# USB.net
KiCad netlist of a schematic drawn in Altium Designer
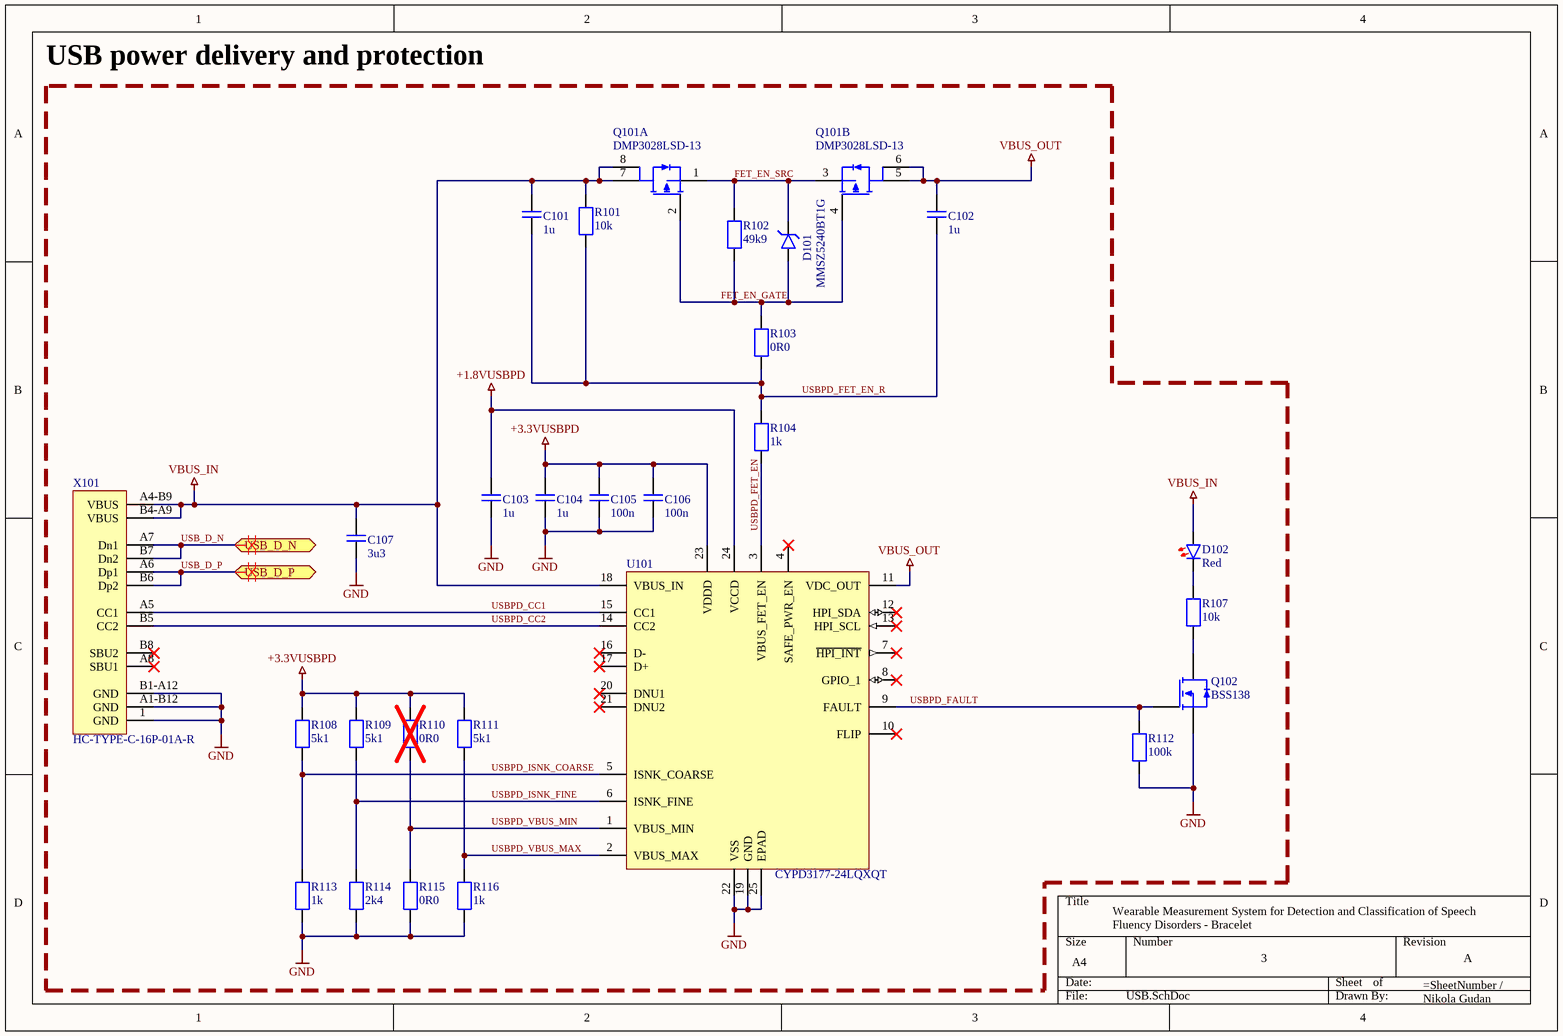
[diagram p0: USB.SchDoc]

(export (version "E")
  (design (tool "Eeschema 10.0.6"))
  (components
    (comp (ref "C101")
      (value "1u")
      (footprint "CAPC0603")
      (description "Ceramic capacitor, 1uF,  50V, X5R")
      (fields (field (name "MFR") "Murata Electronics") (field (name "CHECKED") "Yes"))
      (libsource (lib "NG_Passive") (part "CAPC0603-1u-10"))
    )
    (comp (ref "C102")
      (value "1u")
      (footprint "CAPC0603")
      (description "Ceramic capacitor, 1uF,  50V, X5R")
      (fields (field (name "MFR") "Murata Electronics") (field (name "CHECKED") "Yes"))
      (libsource (lib "NG_Passive") (part "CAPC0603-1u-10"))
    )
    (comp (ref "C103")
      (value "1u")
      (footprint "CAPC0603")
      (description "Ceramic capacitor, 1uF,  50V, X5R")
      (fields (field (name "MFR") "Murata Electronics") (field (name "CHECKED") "Yes"))
      (libsource (lib "NG_Passive") (part "CAPC0603-1u-10"))
    )
    (comp (ref "C104")
      (value "1u")
      (footprint "CAPC0603")
      (description "Ceramic capacitor, 1uF,  50V, X5R")
      (fields (field (name "MFR") "Murata Electronics") (field (name "CHECKED") "Yes"))
      (libsource (lib "NG_Passive") (part "CAPC0603-1u-10"))
    )
    (comp (ref "C105")
      (value "100n")
      (footprint "CAPC0603")
      (description "Ceramic capacitor, 100nF,  50V, X7R")
      (fields (field (name "MFR") "KEMET") (field (name "CHECKED") "Yes"))
      (libsource (lib "NG_Passive") (part "CAPC0603-100n-10"))
    )
    (comp (ref "C106")
      (value "100n")
      (footprint "CAPC0603")
      (description "Ceramic capacitor, 100nF,  50V, X7R")
      (fields (field (name "MFR") "KEMET") (field (name "CHECKED") "Yes"))
      (libsource (lib "NG_Passive") (part "CAPC0603-100n-10"))
    )
    (comp (ref "C107")
      (value "3u3")
      (footprint "CAPC0603")
      (description "Ceramic capacitor, 3.3uF,  25V, X5R")
      (fields (field (name "MFR") "TDK") (field (name "CHECKED") "Yes"))
      (libsource (lib "NG_Passive") (part "CAPC0603-3u3-10"))
    )
    (comp (ref "D101")
      (value "MMSZ5240BT1G")
      (footprint "SODFL368160X117")
      (description "Zener Dioode, 10V, 500mW")
      (fields (field (name "MFR") "onsemi") (field (name "CHECKED") "Yes"))
      (libsource (lib "NG_Active") (part "MMSZ5240BT1G"))
    )
    (comp (ref "D102")
      (value "Red")
      (footprint "LED0603")
      (description "LED Red, 2.3V, 20mA")
      (fields (field (name "MFR") "Würth Elektronik") (field (name "CHECKED") "Yes"))
      (libsource (lib "NG_Active") (part "150060RS75000"))
    )
    (comp (ref "Q101")
      (value "DMP3028LSD-13")
      (footprint "SOIC127P620X175-8")
      (description "MOSFET, 2P-CH, 30V, 6A")
      (fields (field (name "MFR") "Diodes Incorporated") (field (name "CHECKED") "Yes"))
      (libsource (lib "NG_Active") (part "DMP3028LSD-13"))
    )
    (comp (ref "Q102")
      (value "BSS138")
      (footprint "SOT190P240X290-3")
      (description "MOSFET, N-CH, 50V, 220mA")
      (fields (field (name "MFR") "onsemi") (field (name "CHECKED") "Yes"))
      (libsource (lib "NG_Active") (part "BSS138"))
    )
    (comp (ref "R101")
      (value "10k")
      (footprint "RESC0603")
      (description "Thick film resistor, 10kOhm, 100mW")
      (fields (field (name "MFR") "YAGEO") (field (name "CHECKED") "Yes"))
      (libsource (lib "NG_Passive") (part "RES0603-10k-1"))
    )
    (comp (ref "R102")
      (value "49k9")
      (footprint "RESC0603")
      (description "Thick film resistor, 49.9kOhms, 100mW")
      (fields (field (name "MFR") "YAGEO") (field (name "CHECKED") "Yes"))
      (libsource (lib "NG_Passive") (part "RES0603-49k9-1"))
    )
    (comp (ref "R103")
      (value "0R0")
      (footprint "RESC0603")
      (description "Thick film resistor, 0Ohms, 100mW")
      (fields (field (name "MFR") "YAGEO") (field (name "CHECKED") "Yes"))
      (libsource (lib "NG_Passive") (part "RES0603-0R0-1"))
    )
    (comp (ref "R104")
      (value "1k")
      (footprint "RESC0603")
      (description "Thick film resistor, 1k, 100mW")
      (fields (field (name "MFR") "YAGEO") (field (name "CHECKED") "Yes"))
      (libsource (lib "NG_Passive") (part "RES0603-1k-1"))
    )
    (comp (ref "R107")
      (value "10k")
      (footprint "RESC0603")
      (description "Thick film resistor, 10kOhm, 100mW")
      (fields (field (name "MFR") "YAGEO") (field (name "CHECKED") "Yes"))
      (libsource (lib "NG_Passive") (part "RES0603-10k-1"))
    )
    (comp (ref "R108")
      (value "5k1")
      (footprint "RESC0603")
      (description "Thick film resistor, 5.1kOhms, 100mW")
      (fields (field (name "MFR") "YAGEO") (field (name "CHECKED") "Yes"))
      (libsource (lib "NG_Passive") (part "RES0603-5k1-1"))
    )
    (comp (ref "R109")
      (value "5k1")
      (footprint "RESC0603")
      (description "Thick film resistor, 5.1kOhms, 100mW")
      (fields (field (name "MFR") "YAGEO") (field (name "CHECKED") "Yes"))
      (libsource (lib "NG_Passive") (part "RES0603-5k1-1"))
    )
    (comp (ref "R110")
      (value "0R0")
      (footprint "RESC0603")
      (description "Thick film resistor, 0Ohms, 100mW")
      (fields (field (name "MFR") "YAGEO") (field (name "CHECKED") "Yes"))
      (libsource (lib "NG_Passive") (part "RES0603-0R0-1"))
    )
    (comp (ref "R111")
      (value "5k1")
      (footprint "RESC0603")
      (description "Thick film resistor, 5.1kOhms, 100mW")
      (fields (field (name "MFR") "YAGEO") (field (name "CHECKED") "Yes"))
      (libsource (lib "NG_Passive") (part "RES0603-5k1-1"))
    )
    (comp (ref "R112")
      (value "100k")
      (footprint "RESC0603")
      (description "Thick film resistor, 100kOhms, 100mW")
      (fields (field (name "MFR") "YAGEO") (field (name "CHECKED") "Yes"))
      (libsource (lib "NG_Passive") (part "RES0603-100k-1"))
    )
    (comp (ref "R113")
      (value "1k")
      (footprint "RESC0603")
      (description "Thick film resistor, 1k, 100mW")
      (fields (field (name "MFR") "YAGEO") (field (name "CHECKED") "Yes"))
      (libsource (lib "NG_Passive") (part "RES0603-1k-1"))
    )
    (comp (ref "R114")
      (value "2k4")
      (footprint "RESC0603")
      (description "Thick film resistor, 2.4kOhms, 100mW")
      (fields (field (name "MFR") "YAGEO") (field (name "CHECKED") "Yes"))
      (libsource (lib "NG_Passive") (part "RES0603-2k4-1"))
    )
    (comp (ref "R115")
      (value "0R0")
      (footprint "RESC0603")
      (description "Thick film resistor, 0Ohms, 100mW")
      (fields (field (name "MFR") "YAGEO") (field (name "CHECKED") "Yes"))
      (libsource (lib "NG_Passive") (part "RES0603-0R0-1"))
    )
    (comp (ref "R116")
      (value "1k")
      (footprint "RESC0603")
      (description "Thick film resistor, 1k, 100mW")
      (fields (field (name "MFR") "YAGEO") (field (name "CHECKED") "Yes"))
      (libsource (lib "NG_Passive") (part "RES0603-1k-1"))
    )
    (comp (ref "U101")
      (value "CYPD3177-24LQXQT")
      (footprint "QFN50P410X410X100-24EP")
      (description "Generic Description")
      (fields (field (name "MFR") "Infineon Technologies") (field (name "CHECKED") "Yes"))
      (libsource (lib "NG_Analog") (part "CYPD3177-24LQXQT"))
    )
    (comp (ref "X101")
      (value "HC-TYPE-C-16P-01A-R")
      (footprint "GCT_USB4105-GF-A")
      (description "USB TYPE-C 3.1, 3A")
      (fields (field (name "MFR") "GCT") (field (name "CHECKED") "Yes"))
      (libsource (lib "NG_Mechanical") (part "CONN USB 2.0 TYPE C"))
    )
  )
  (nets
    (net (code "1") (name "+1.8VUSBPD") (class "Default")
      (node (ref "C103") (pin "2") (pinfunction "2_2") (pintype "passive"))
      (node (ref "U101") (pin "24") (pinfunction "VCCD_24") (pintype "power_in"))
    )
    (net (code "2") (name "+3.3VUSBPD") (class "Default")
      (node (ref "C104") (pin "2") (pinfunction "2_2") (pintype "passive"))
      (node (ref "C105") (pin "2") (pinfunction "2_2") (pintype "passive"))
      (node (ref "C106") (pin "2") (pinfunction "2_2") (pintype "passive"))
      (node (ref "R108") (pin "2") (pinfunction "2_2") (pintype "passive"))
      (node (ref "R109") (pin "2") (pinfunction "2_2") (pintype "passive"))
      (node (ref "R110") (pin "2") (pinfunction "2_2") (pintype "passive"))
      (node (ref "R111") (pin "2") (pinfunction "2_2") (pintype "passive"))
      (node (ref "U101") (pin "23") (pinfunction "VDDD_23") (pintype "power_in"))
    )
    (net (code "3") (name "/FET_EN_GATE") (class "Default")
      (node (ref "D101") (pin "2") (pinfunction "2_2") (pintype "passive"))
      (node (ref "Q101") (pin "2") (pinfunction "G1_2") (pintype "power_in"))
      (node (ref "Q101") (pin "4") (pinfunction "G2_4") (pintype "power_in"))
      (node (ref "R102") (pin "1") (pinfunction "1_1") (pintype "passive"))
      (node (ref "R103") (pin "2") (pinfunction "2_2") (pintype "passive"))
    )
    (net (code "4") (name "/FET_EN_SRC") (class "Default")
      (node (ref "D101") (pin "1") (pinfunction "1_1") (pintype "passive"))
      (node (ref "Q101") (pin "1") (pinfunction "S1_1") (pintype "power_in"))
      (node (ref "Q101") (pin "3") (pinfunction "S2_3") (pintype "power_in"))
      (node (ref "R102") (pin "2") (pinfunction "2_2") (pintype "passive"))
    )
    (net (code "5") (name "/USBPD_CC1") (class "Default")
      (node (ref "U101") (pin "15") (pinfunction "CC1_15") (pintype "passive"))
      (node (ref "X101") (pin "A5") (pinfunction "CC1_A5") (pintype "passive"))
    )
    (net (code "6") (name "/USBPD_CC2") (class "Default")
      (node (ref "U101") (pin "14") (pinfunction "CC2_14") (pintype "passive"))
      (node (ref "X101") (pin "B5") (pinfunction "CC2_B5") (pintype "passive"))
    )
    (net (code "7") (name "/USBPD_FAULT") (class "Default")
      (node (ref "Q102") (pin "1") (pinfunction "G_1") (pintype "passive"))
      (node (ref "R112") (pin "2") (pinfunction "2_2") (pintype "passive"))
      (node (ref "U101") (pin "9") (pinfunction "FAULT_9") (pintype "passive"))
    )
    (net (code "8") (name "/USBPD_FET_EN") (class "Default")
      (node (ref "R104") (pin "1") (pinfunction "1_1") (pintype "passive"))
      (node (ref "U101") (pin "3") (pinfunction "VBUS_FET_EN_3") (pintype "passive"))
    )
    (net (code "9") (name "/USBPD_FET_EN_R") (class "Default")
      (node (ref "C101") (pin "1") (pinfunction "1_1") (pintype "passive"))
      (node (ref "C102") (pin "1") (pinfunction "1_1") (pintype "passive"))
      (node (ref "R101") (pin "1") (pinfunction "1_1") (pintype "passive"))
      (node (ref "R103") (pin "1") (pinfunction "1_1") (pintype "passive"))
      (node (ref "R104") (pin "2") (pinfunction "2_2") (pintype "passive"))
    )
    (net (code "10") (name "/USBPD_ISNK_COARSE") (class "Default")
      (node (ref "R108") (pin "1") (pinfunction "1_1") (pintype "passive"))
      (node (ref "R113") (pin "2") (pinfunction "2_2") (pintype "passive"))
      (node (ref "U101") (pin "5") (pinfunction "ISNK_COARSE_5") (pintype "passive"))
    )
    (net (code "11") (name "/USBPD_ISNK_FINE") (class "Default")
      (node (ref "R109") (pin "1") (pinfunction "1_1") (pintype "passive"))
      (node (ref "R114") (pin "2") (pinfunction "2_2") (pintype "passive"))
      (node (ref "U101") (pin "6") (pinfunction "ISNK_FINE_6") (pintype "passive"))
    )
    (net (code "12") (name "/USBPD_VBUS_MAX") (class "Default")
      (node (ref "R111") (pin "1") (pinfunction "1_1") (pintype "passive"))
      (node (ref "R116") (pin "2") (pinfunction "2_2") (pintype "passive"))
      (node (ref "U101") (pin "2") (pinfunction "VBUS_MAX_2") (pintype "passive"))
    )
    (net (code "13") (name "/USBPD_VBUS_MIN") (class "Default")
      (node (ref "R110") (pin "1") (pinfunction "1_1") (pintype "passive"))
      (node (ref "R115") (pin "2") (pinfunction "2_2") (pintype "passive"))
      (node (ref "U101") (pin "1") (pinfunction "VBUS_MIN_1") (pintype "passive"))
    )
    (net (code "14") (name "/USB_D_N") (class "Default")
      (node (ref "X101") (pin "A7") (pinfunction "Dn1_A7") (pintype "passive"))
      (node (ref "X101") (pin "B7") (pinfunction "Dn2_B7") (pintype "passive"))
    )
    (net (code "15") (name "/USB_D_P") (class "Default")
      (node (ref "X101") (pin "A6") (pinfunction "Dp1_A6") (pintype "passive"))
      (node (ref "X101") (pin "B6") (pinfunction "Dp2_B6") (pintype "passive"))
    )
    (net (code "16") (name "GND") (class "Default")
      (node (ref "C103") (pin "1") (pinfunction "1_1") (pintype "passive"))
      (node (ref "C104") (pin "1") (pinfunction "1_1") (pintype "passive"))
      (node (ref "C105") (pin "1") (pinfunction "1_1") (pintype "passive"))
      (node (ref "C106") (pin "1") (pinfunction "1_1") (pintype "passive"))
      (node (ref "C107") (pin "1") (pinfunction "1_1") (pintype "passive"))
      (node (ref "Q102") (pin "2") (pinfunction "S_2") (pintype "passive"))
      (node (ref "R112") (pin "1") (pinfunction "1_1") (pintype "passive"))
      (node (ref "R113") (pin "1") (pinfunction "1_1") (pintype "passive"))
      (node (ref "R114") (pin "1") (pinfunction "1_1") (pintype "passive"))
      (node (ref "R115") (pin "1") (pinfunction "1_1") (pintype "passive"))
      (node (ref "R116") (pin "1") (pinfunction "1_1") (pintype "passive"))
      (node (ref "U101") (pin "19") (pinfunction "GND_19") (pintype "power_in"))
      (node (ref "U101") (pin "22") (pinfunction "VSS_22") (pintype "power_in"))
      (node (ref "U101") (pin "25") (pinfunction "EPAD_25") (pintype "power_in"))
      (node (ref "X101") (pin "1") (pinfunction "GND_1") (pintype "power_in"))
      (node (ref "X101") (pin "A1-B12") (pinfunction "GND_A1-B12") (pintype "power_in"))
      (node (ref "X101") (pin "B1-A12") (pinfunction "GND_B1-A12") (pintype "power_in"))
    )
    (net (code "17") (name "Net-(D102-Pad1)") (class "Default")
      (node (ref "D102") (pin "1") (pinfunction "1_1") (pintype "passive"))
      (node (ref "R107") (pin "2") (pinfunction "2_2") (pintype "passive"))
    )
    (net (code "18") (name "Net-(Q102-D)") (class "Default")
      (node (ref "Q102") (pin "3") (pinfunction "D_3") (pintype "passive"))
      (node (ref "R107") (pin "1") (pinfunction "1_1") (pintype "passive"))
    )
    (net (code "19") (name "VBUS_IN") (class "Default")
      (node (ref "C101") (pin "2") (pinfunction "2_2") (pintype "passive"))
      (node (ref "C107") (pin "2") (pinfunction "2_2") (pintype "passive"))
      (node (ref "D102") (pin "2") (pinfunction "2_2") (pintype "passive"))
      (node (ref "Q101") (pin "7") (pinfunction "D1_7") (pintype "power_in"))
      (node (ref "Q101") (pin "8") (pinfunction "D1_8") (pintype "power_in"))
      (node (ref "R101") (pin "2") (pinfunction "2_2") (pintype "passive"))
      (node (ref "U101") (pin "18") (pinfunction "VBUS_IN_18") (pintype "power_in"))
      (node (ref "X101") (pin "A4-B9") (pinfunction "VBUS_A4-B9") (pintype "power_in"))
      (node (ref "X101") (pin "B4-A9") (pinfunction "VBUS_B4-A9") (pintype "power_in"))
    )
    (net (code "20") (name "VBUS_OUT") (class "Default")
      (node (ref "C102") (pin "2") (pinfunction "2_2") (pintype "passive"))
      (node (ref "Q101") (pin "5") (pinfunction "D2_5") (pintype "power_in"))
      (node (ref "Q101") (pin "6") (pinfunction "D2_6") (pintype "power_in"))
      (node (ref "U101") (pin "11") (pinfunction "VDC_OUT_11") (pintype "passive"))
    )
    (net (code "21") (name "unconnected-(U101-D+-Pad17)") (class "Default")
      (node (ref "U101") (pin "17") (pinfunction "D+_17") (pintype "passive+no_connect"))
    )
    (net (code "22") (name "unconnected-(U101-D--Pad16)") (class "Default")
      (node (ref "U101") (pin "16") (pinfunction "D-_16") (pintype "passive+no_connect"))
    )
    (net (code "23") (name "unconnected-(U101-DNU1-Pad20)") (class "Default")
      (node (ref "U101") (pin "20") (pinfunction "DNU1_20") (pintype "passive+no_connect"))
    )
    (net (code "24") (name "unconnected-(U101-DNU2-Pad21)") (class "Default")
      (node (ref "U101") (pin "21") (pinfunction "DNU2_21") (pintype "passive+no_connect"))
    )
    (net (code "25") (name "unconnected-(U101-FLIP-Pad10)") (class "Default")
      (node (ref "U101") (pin "10") (pinfunction "FLIP_10") (pintype "passive+no_connect"))
    )
    (net (code "26") (name "unconnected-(U101-GPIO_1-Pad8)") (class "Default")
      (node (ref "U101") (pin "8") (pinfunction "GPIO_1_8") (pintype "bidirectional+no_connect"))
    )
    (net (code "27") (name "unconnected-(U101-HPI_SCL-Pad13)") (class "Default")
      (node (ref "U101") (pin "13") (pinfunction "HPI_SCL_13") (pintype "input+no_connect"))
    )
    (net (code "28") (name "unconnected-(U101-HPI_SDA-Pad12)") (class "Default")
      (node (ref "U101") (pin "12") (pinfunction "HPI_SDA_12") (pintype "bidirectional+no_connect"))
    )
    (net (code "29") (name "unconnected-(U101-SAFE_PWR_EN-Pad4)") (class "Default")
      (node (ref "U101") (pin "4") (pinfunction "SAFE_PWR_EN_4") (pintype "passive+no_connect"))
    )
    (net (code "30") (name "unconnected-(U101-~{HPI_INT}-Pad7)") (class "Default")
      (node (ref "U101") (pin "7") (pinfunction "~{HPI_INT}_7") (pintype "output+no_connect"))
    )
    (net (code "31") (name "unconnected-(X101-SBU1-PadA8)") (class "Default")
      (node (ref "X101") (pin "A8") (pinfunction "SBU1_A8") (pintype "passive+no_connect"))
    )
    (net (code "32") (name "unconnected-(X101-SBU2-PadB8)") (class "Default")
      (node (ref "X101") (pin "B8") (pinfunction "SBU2_B8") (pintype "passive+no_connect"))
    )
  )
)
